# wisp-6-peripherals.net
KiCad netlist of a schematic drawn in Altium Designer
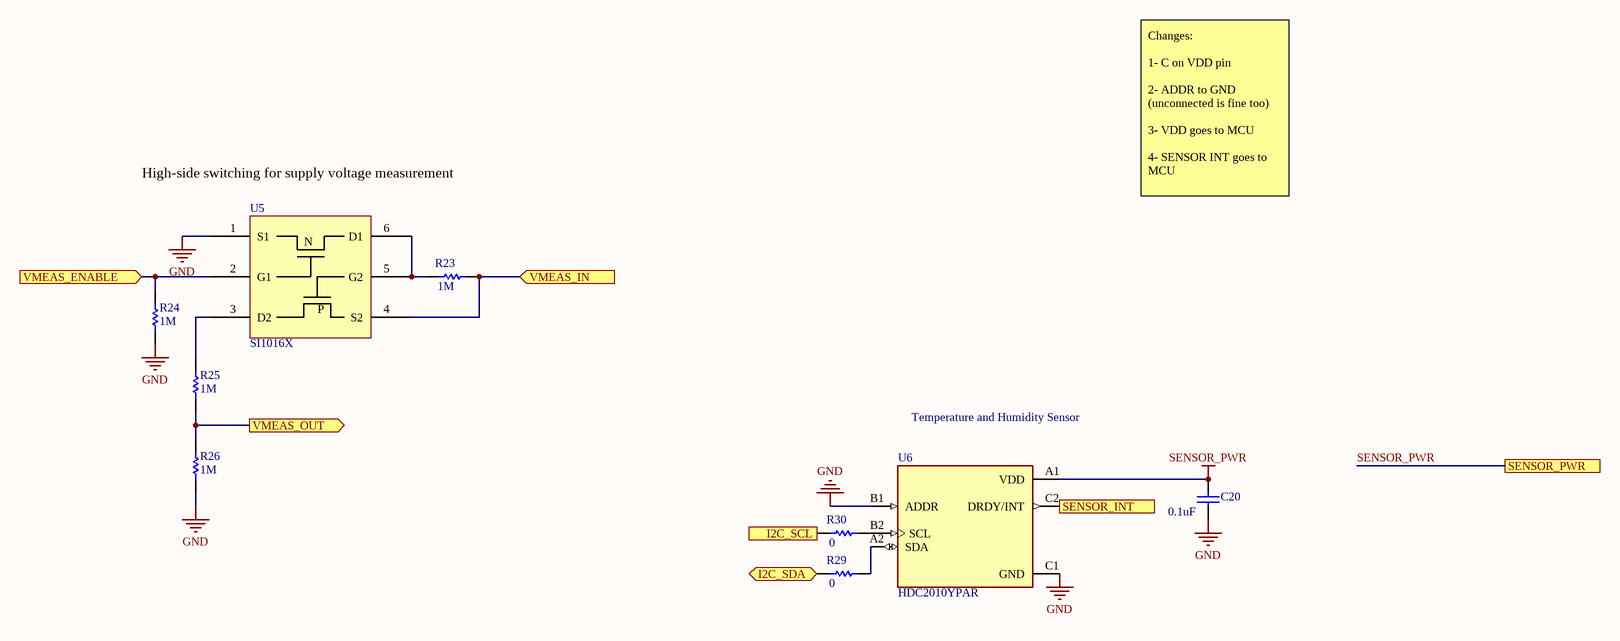
[diagram p0: wisp-6-peripherals.SchDoc]

(export (version "E")
  (design (tool "Eeschema 10.0.6"))
  (components
    (comp (ref "C20")
      (value "0.1uF")
      (footprint "0402")
      (description "Ceramic Capacitor (Surface Mount)")
      (fields (field (name "MANUFACTURER") "Generic Ceramic Chip Cap (TBD)") (field (name "Comment") "Cap"))
      (libsource (lib "WISP_AD10") (part "Cap"))
    )
    (comp (ref "R23")
      (value "1M")
      (footprint "0402")
      (description "Chip Resistor (Surface Mount)")
      (fields (field (name "MANUFACTURER") "Generic Chip Res (TBD)") (field (name "Comment") "Res"))
      (libsource (lib "WISP_AD10") (part "Res"))
    )
    (comp (ref "R24")
      (value "1M")
      (footprint "0402")
      (description "Chip Resistor (Surface Mount)")
      (fields (field (name "MANUFACTURER") "Generic Chip Res (TBD)") (field (name "Comment") "Res"))
      (libsource (lib "WISP_AD10") (part "Res"))
    )
    (comp (ref "R25")
      (value "1M")
      (footprint "0402")
      (description "Chip Resistor (Surface Mount)")
      (fields (field (name "MANUFACTURER") "Generic Chip Res (TBD)") (field (name "Comment") "Res"))
      (libsource (lib "WISP_AD10") (part "Res"))
    )
    (comp (ref "R26")
      (value "1M")
      (footprint "0402")
      (description "Chip Resistor (Surface Mount)")
      (fields (field (name "MANUFACTURER") "Generic Chip Res (TBD)") (field (name "Comment") "Res"))
      (libsource (lib "WISP_AD10") (part "Res"))
    )
    (comp (ref "R29")
      (value "0")
      (footprint "0402")
      (description "Chip Resistor (Surface Mount)")
      (fields (field (name "MANUFACTURER") "Generic Chip Res (TBD)") (field (name "Comment") "Res"))
      (libsource (lib "WISP_AD10") (part "Res"))
    )
    (comp (ref "R30")
      (value "0")
      (footprint "0402")
      (description "Chip Resistor (Surface Mount)")
      (fields (field (name "MANUFACTURER") "Generic Chip Res (TBD)") (field (name "Comment") "Res"))
      (libsource (lib "WISP_AD10") (part "Res"))
    )
    (comp (ref "U5")
      (value "SI1016X")
      (footprint "SC-89-6 Vishay")
      (description "NMOS and PMOS array")
      (libsource (lib "WISP_AD10") (part "SI1016X"))
    )
    (comp (ref "U6")
      (value "HDC2010YPAR")
      (footprint "BGA6C100X50P2X3_HDC2010YPAR")
      (description "Humidity Temperature Sensor 0 ~ 100% RH IÂ²C Â±2% 8s Surface Mount")
      (fields (field (name "MF") "Texas Instruments") (field (name "DIGI-KEY_PART_NUMBER") "296-47774-1-ND"))
      (libsource (lib "HDC2010YPAR") (part "HDC2010YPAR"))
    )
  )
  (nets
    (net (code "1") (name "/I2C_SCL") (class "Default")
      (node (ref "R30") (pin "2") (pinfunction "2_2") (pintype "passive"))
    )
    (net (code "2") (name "/I2C_SDA") (class "Default")
      (node (ref "R29") (pin "2") (pinfunction "2_2") (pintype "passive"))
    )
    (net (code "3") (name "/SENSOR_INT") (class "Default")
      (node (ref "U6") (pin "C2") (pinfunction "DRDY/INT_C2") (pintype "output"))
    )
    (net (code "4") (name "/VMEAS_ENABLE") (class "Default")
      (node (ref "R24") (pin "2") (pinfunction "2_2") (pintype "passive"))
      (node (ref "U5") (pin "2") (pinfunction "G1_2") (pintype "passive"))
    )
    (net (code "5") (name "/VMEAS_IN") (class "Default")
      (node (ref "R23") (pin "1") (pinfunction "1_1") (pintype "passive"))
      (node (ref "U5") (pin "4") (pinfunction "S2_4") (pintype "passive"))
    )
    (net (code "6") (name "/VMEAS_OUT") (class "Default")
      (node (ref "R25") (pin "1") (pinfunction "1_1") (pintype "passive"))
      (node (ref "R26") (pin "2") (pinfunction "2_2") (pintype "passive"))
    )
    (net (code "7") (name "GND") (class "Default")
      (node (ref "C20") (pin "1") (pinfunction "1_1") (pintype "passive"))
      (node (ref "R24") (pin "1") (pinfunction "1_1") (pintype "passive"))
      (node (ref "R26") (pin "1") (pinfunction "1_1") (pintype "passive"))
      (node (ref "U5") (pin "1") (pinfunction "S1_1") (pintype "passive"))
      (node (ref "U6") (pin "B1") (pinfunction "ADDR_B1") (pintype "input"))
      (node (ref "U6") (pin "C1") (pinfunction "GND_C1") (pintype "power_in"))
    )
    (net (code "8") (name "Net-(U5-D1)") (class "Default")
      (node (ref "R23") (pin "2") (pinfunction "2_2") (pintype "passive"))
      (node (ref "U5") (pin "5") (pinfunction "G2_5") (pintype "passive"))
      (node (ref "U5") (pin "6") (pinfunction "D1_6") (pintype "passive"))
    )
    (net (code "9") (name "Net-(U5-D2)") (class "Default")
      (node (ref "R25") (pin "2") (pinfunction "2_2") (pintype "passive"))
      (node (ref "U5") (pin "3") (pinfunction "D2_3") (pintype "passive"))
    )
    (net (code "10") (name "Net-(U6-SCL)") (class "Default")
      (node (ref "R30") (pin "1") (pinfunction "1_1") (pintype "passive"))
      (node (ref "U6") (pin "B2") (pinfunction "SCL_B2") (pintype "input"))
    )
    (net (code "11") (name "Net-(U6-SDA)") (class "Default")
      (node (ref "R29") (pin "1") (pinfunction "1_1") (pintype "passive"))
      (node (ref "U6") (pin "A2") (pinfunction "SDA_A2") (pintype "bidirectional"))
    )
    (net (code "12") (name "SENSOR_PWR") (class "Default")
      (node (ref "C20") (pin "2") (pinfunction "2_2") (pintype "passive"))
      (node (ref "U6") (pin "A1") (pinfunction "VDD_A1") (pintype "power_in"))
    )
  )
)
